# ko_relay.net
KiCad netlist of a schematic drawn in EAGLE
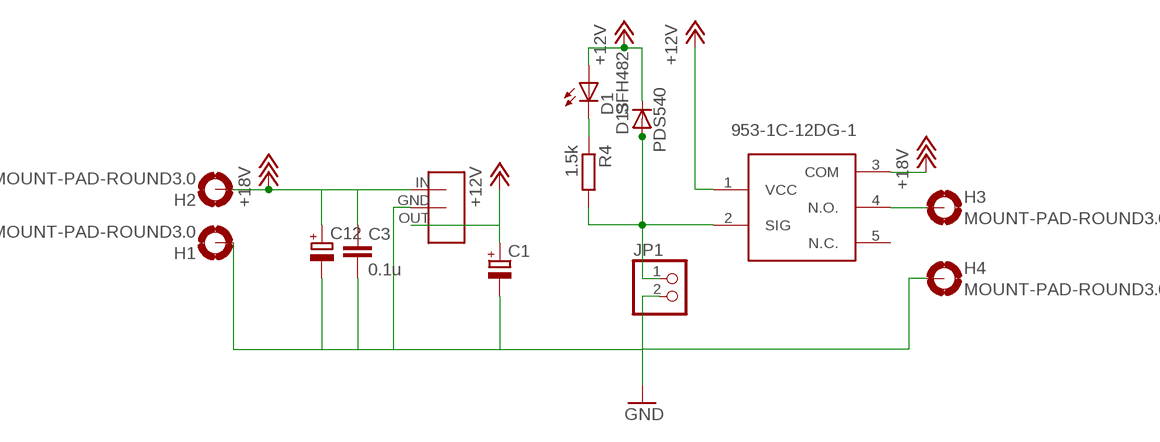
[diagram p0: schematic, sheet 1]

(export (version "E")
  (design (tool "Eeschema 10.0.6"))
  (components
    (comp (ref "C1")
      (value "CPOL-EUE2.5-6")
      (footprint "eagle-import:E2,5-6")
      (libsource (lib "eagle-import") (part "CPOL-EUE2.5-6"))
    )
    (comp (ref "C3")
      (value "0.1u")
      (footprint "eagle-import:C0603K")
      (libsource (lib "eagle-import") (part "C-EUC0603K"))
    )
    (comp (ref "C12")
      (value "CPOL-EUE2.5-6")
      (footprint "eagle-import:E2,5-6")
      (libsource (lib "eagle-import") (part "CPOL-EUE2.5-6"))
    )
    (comp (ref "D1")
      (value "SFH482")
      (footprint "eagle-import:SFH482")
      (libsource (lib "eagle-import") (part "SFH482"))
    )
    (comp (ref "D13")
      (value "PDS540")
      (footprint "eagle-import:POWER_DI_5")
      (libsource (lib "eagle-import") (part "PDS540"))
    )
    (comp (ref "H1")
      (value "MOUNT-PAD-ROUND3.0")
      (footprint "eagle-import:3,0-PAD")
      (libsource (lib "eagle-import") (part "MOUNT-PAD-ROUND3.0"))
    )
    (comp (ref "H2")
      (value "MOUNT-PAD-ROUND3.0")
      (footprint "eagle-import:3,0-PAD")
      (libsource (lib "eagle-import") (part "MOUNT-PAD-ROUND3.0"))
    )
    (comp (ref "H3")
      (value "MOUNT-PAD-ROUND3.0")
      (footprint "eagle-import:3,0-PAD")
      (libsource (lib "eagle-import") (part "MOUNT-PAD-ROUND3.0"))
    )
    (comp (ref "H4")
      (value "MOUNT-PAD-ROUND3.0")
      (footprint "eagle-import:3,0-PAD")
      (libsource (lib "eagle-import") (part "MOUNT-PAD-ROUND3.0"))
    )
    (comp (ref "JP1")
      (value "PINHD-1X2")
      (footprint "eagle-import:1X02")
      (libsource (lib "eagle-import") (part "PINHD-1X2"))
    )
    (comp (ref "R4")
      (value "1.5k")
      (footprint "eagle-import:R0603")
      (libsource (lib "eagle-import") (part "R-EU_R0603"))
    )
    (comp (ref "U$1")
      (value "HOGE")
      (footprint "eagle-import:HOGE")
      (libsource (lib "eagle-import") (part "HOGE"))
    )
    (comp (ref "U$8")
      (value "RELAY(953-1C-12DG-1)")
      (footprint "eagle-import:953-1C-12DG-1")
      (libsource (lib "eagle-import") (part "RELAY(953-1C-12DG-1)"))
    )
  )
  (nets
    (net (code "1") (name "+12V") (class "Default")
      (node (ref "C1") (pin "+") (pinfunction "+_+") (pintype "passive"))
      (node (ref "D1") (pin "A") (pinfunction "A_A") (pintype "passive"))
      (node (ref "D13") (pin "K") (pinfunction "C_K") (pintype "passive"))
      (node (ref "U$1") (pin "OUT") (pinfunction "OUT_OUT") (pintype "bidirectional"))
      (node (ref "U$8") (pin "1") (pinfunction "VCC_1") (pintype "bidirectional"))
    )
    (net (code "2") (name "+18V") (class "Default")
      (node (ref "C12") (pin "+") (pinfunction "+_+") (pintype "passive"))
      (node (ref "C3") (pin "1") (pinfunction "1_1") (pintype "passive"))
      (node (ref "H2") (pin "B3,0") (pinfunction "MOUNT_B3,0") (pintype "passive"))
      (node (ref "U$1") (pin "IN") (pinfunction "IN_IN") (pintype "bidirectional"))
      (node (ref "U$8") (pin "3") (pinfunction "COM_3") (pintype "bidirectional"))
    )
    (net (code "3") (name "GND") (class "Default")
      (node (ref "C1") (pin "-") (pinfunction "-_-") (pintype "passive"))
      (node (ref "C12") (pin "-") (pinfunction "-_-") (pintype "passive"))
      (node (ref "C3") (pin "2") (pinfunction "2_2") (pintype "passive"))
      (node (ref "H1") (pin "B3,0") (pinfunction "MOUNT_B3,0") (pintype "passive"))
      (node (ref "H4") (pin "B3,0") (pinfunction "MOUNT_B3,0") (pintype "passive"))
      (node (ref "JP1") (pin "2") (pinfunction "2_2") (pintype "passive"))
      (node (ref "U$1") (pin "GND") (pinfunction "GND_GND") (pintype "bidirectional"))
    )
    (net (code "4") (name "Net-(D1-C)") (class "Default")
      (node (ref "D1") (pin "K") (pinfunction "C_K") (pintype "passive"))
      (node (ref "R4") (pin "1") (pinfunction "1_1") (pintype "passive"))
    )
    (net (code "5") (name "Net-(D13-A)") (class "Default")
      (node (ref "D13") (pin "A1") (pinfunction "A1_A1") (pintype "passive"))
      (node (ref "D13") (pin "A2") (pinfunction "A_A2") (pintype "passive"))
      (node (ref "JP1") (pin "1") (pinfunction "1_1") (pintype "passive"))
      (node (ref "R4") (pin "2") (pinfunction "2_2") (pintype "passive"))
      (node (ref "U$8") (pin "2") (pinfunction "SIG_2") (pintype "bidirectional"))
    )
    (net (code "6") (name "Net-(H3-MOUNT)") (class "Default")
      (node (ref "H3") (pin "B3,0") (pinfunction "MOUNT_B3,0") (pintype "passive"))
      (node (ref "U$8") (pin "4") (pinfunction "N.O._4") (pintype "bidirectional"))
    )
    (net (code "7") (name "unconnected-(U$8-N.C.-Pad5)") (class "Default")
      (node (ref "U$8") (pin "5") (pinfunction "N.C._5") (pintype "bidirectional"))
    )
  )
)
